# Sheet1.net
KiCad netlist of a schematic drawn in Altium Designer
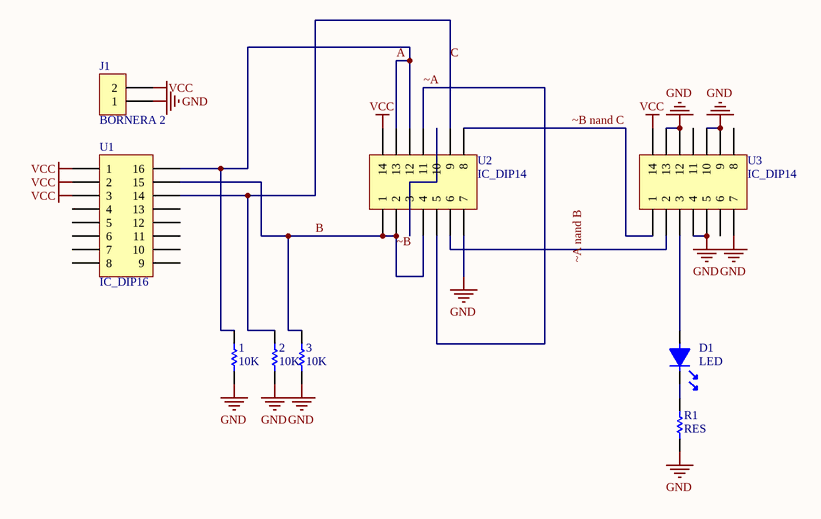
[diagram p0: Sheet1.SchDoc]

(export (version "E")
  (design (tool "Eeschema 10.0.6"))
  (components
    (comp (ref "1") (value "10K") (footprint "RES400") (libsource (lib "LIBEBAL") (part "RES")))
    (comp (ref "2") (value "10K") (footprint "RES400") (libsource (lib "LIBEBAL") (part "RES")))
    (comp (ref "3") (value "10K") (footprint "RES400") (libsource (lib "LIBEBAL") (part "RES")))
    (comp (ref "D1") (value "LED") (footprint "LED3") (libsource (lib "LIBEBAL") (part "LED")))
    (comp (ref "J1")
      (value "BORNERA 2")
      (footprint "BORNERA2")
      (libsource (lib "LIBEBAL") (part "BORNERA 2"))
    )
    (comp (ref "R1") (value "RES") (footprint "RES400") (libsource (lib "LIBEBAL") (part "RES")))
    (comp (ref "U1") (value "IC_DIP16") (footprint "DIP16") (libsource (lib "LIBEBAL") (part "IC_DIP16")))
    (comp (ref "U2") (value "IC_DIP14") (footprint "DIP14") (libsource (lib "LIBEBAL") (part "IC_DIP14")))
    (comp (ref "U3") (value "IC_DIP14") (footprint "DIP14") (libsource (lib "LIBEBAL") (part "IC_DIP14")))
  )
  (nets
    (net (code "1") (name "/A") (class "Default")
      (node (ref "1") (pin "1") (pinfunction "1_1") (pintype "passive"))
      (node (ref "U1") (pin "16") (pinfunction "16_16") (pintype "passive"))
      (node (ref "U2") (pin "12") (pinfunction "12_12") (pintype "passive"))
      (node (ref "U2") (pin "13") (pinfunction "13_13") (pintype "passive"))
    )
    (net (code "2") (name "/B") (class "Default")
      (node (ref "3") (pin "1") (pinfunction "1_1") (pintype "passive"))
      (node (ref "U1") (pin "15") (pinfunction "15_15") (pintype "passive"))
      (node (ref "U2") (pin "1") (pinfunction "1_1") (pintype "passive"))
      (node (ref "U2") (pin "2") (pinfunction "2_2") (pintype "passive"))
      (node (ref "U2") (pin "4") (pinfunction "4_4") (pintype "passive"))
    )
    (net (code "3") (name "/C") (class "Default")
      (node (ref "2") (pin "1") (pinfunction "1_1") (pintype "passive"))
      (node (ref "U1") (pin "14") (pinfunction "14_14") (pintype "passive"))
      (node (ref "U2") (pin "9") (pinfunction "9_9") (pintype "passive"))
    )
    (net (code "4") (name "/~A") (class "Default")
      (node (ref "U2") (pin "11") (pinfunction "11_11") (pintype "passive"))
      (node (ref "U2") (pin "5") (pinfunction "5_5") (pintype "passive"))
    )
    (net (code "6") (name "/~B nand C") (class "Default")
      (node (ref "U2") (pin "8") (pinfunction "8_8") (pintype "passive"))
      (node (ref "U3") (pin "1") (pinfunction "1_1") (pintype "passive"))
    )
    (net (code "7") (name "GND") (class "Default")
      (node (ref "1") (pin "2") (pinfunction "2_2") (pintype "passive"))
      (node (ref "2") (pin "2") (pinfunction "2_2") (pintype "passive"))
      (node (ref "3") (pin "2") (pinfunction "2_2") (pintype "passive"))
      (node (ref "J1") (pin "1") (pinfunction "1_1") (pintype "passive"))
      (node (ref "R1") (pin "1") (pinfunction "1_1") (pintype "passive"))
      (node (ref "U2") (pin "7") (pinfunction "7_7") (pintype "passive"))
      (node (ref "U3") (pin "10") (pinfunction "10_10") (pintype "passive"))
      (node (ref "U3") (pin "12") (pinfunction "12_12") (pintype "passive"))
      (node (ref "U3") (pin "13") (pinfunction "13_13") (pintype "passive"))
      (node (ref "U3") (pin "4") (pinfunction "4_4") (pintype "passive"))
      (node (ref "U3") (pin "5") (pinfunction "5_5") (pintype "passive"))
      (node (ref "U3") (pin "7") (pinfunction "7_7") (pintype "passive"))
      (node (ref "U3") (pin "9") (pinfunction "9_9") (pintype "passive"))
    )
    (net (code "8") (name "Net-(D1-Pad1)") (class "Default")
      (node (ref "D1") (pin "1") (pinfunction "1_1") (pintype "passive"))
      (node (ref "U3") (pin "3") (pinfunction "3_3") (pintype "passive"))
    )
    (net (code "9") (name "Net-(D1-Pad2)") (class "Default")
      (node (ref "D1") (pin "2") (pinfunction "2_2") (pintype "passive"))
      (node (ref "R1") (pin "2") (pinfunction "2_2") (pintype "passive"))
    )
    (net (code "10") (name "Net-(U2-Pad6)") (class "Default")
      (node (ref "U2") (pin "6") (pinfunction "6_6") (pintype "passive"))
      (node (ref "U3") (pin "2") (pinfunction "2_2") (pintype "passive"))
    )
    (net (code "11") (name "Net-(U2-Pad10)") (class "Default")
      (node (ref "U2") (pin "10") (pinfunction "10_10") (pintype "passive"))
      (node (ref "U2") (pin "3") (pinfunction "3_3") (pintype "passive"))
    )
    (net (code "12") (name "VCC") (class "Default")
      (node (ref "J1") (pin "2") (pinfunction "2_2") (pintype "passive"))
      (node (ref "U1") (pin "1") (pinfunction "1_1") (pintype "passive"))
      (node (ref "U1") (pin "2") (pinfunction "2_2") (pintype "passive"))
      (node (ref "U1") (pin "3") (pinfunction "3_3") (pintype "passive"))
      (node (ref "U2") (pin "14") (pinfunction "14_14") (pintype "passive"))
      (node (ref "U3") (pin "14") (pinfunction "14_14") (pintype "passive"))
    )
    (net (code "13") (name "unconnected-(U1-Pad4)") (class "Default")
      (node (ref "U1") (pin "4") (pinfunction "4_4") (pintype "passive"))
    )
    (net (code "14") (name "unconnected-(U1-Pad5)") (class "Default")
      (node (ref "U1") (pin "5") (pinfunction "5_5") (pintype "passive"))
    )
    (net (code "15") (name "unconnected-(U1-Pad6)") (class "Default")
      (node (ref "U1") (pin "6") (pinfunction "6_6") (pintype "passive"))
    )
    (net (code "16") (name "unconnected-(U1-Pad7)") (class "Default")
      (node (ref "U1") (pin "7") (pinfunction "7_7") (pintype "passive"))
    )
    (net (code "17") (name "unconnected-(U1-Pad8)") (class "Default")
      (node (ref "U1") (pin "8") (pinfunction "8_8") (pintype "passive"))
    )
    (net (code "18") (name "unconnected-(U1-Pad9)") (class "Default")
      (node (ref "U1") (pin "9") (pinfunction "9_9") (pintype "passive"))
    )
    (net (code "19") (name "unconnected-(U1-Pad10)") (class "Default")
      (node (ref "U1") (pin "10") (pinfunction "10_10") (pintype "passive"))
    )
    (net (code "20") (name "unconnected-(U1-Pad11)") (class "Default")
      (node (ref "U1") (pin "11") (pinfunction "11_11") (pintype "passive"))
    )
    (net (code "21") (name "unconnected-(U1-Pad12)") (class "Default")
      (node (ref "U1") (pin "12") (pinfunction "12_12") (pintype "passive"))
    )
    (net (code "22") (name "unconnected-(U1-Pad13)") (class "Default")
      (node (ref "U1") (pin "13") (pinfunction "13_13") (pintype "passive"))
    )
    (net (code "23") (name "unconnected-(U3-Pad6)") (class "Default")
      (node (ref "U3") (pin "6") (pinfunction "6_6") (pintype "passive"))
    )
    (net (code "24") (name "unconnected-(U3-Pad8)") (class "Default")
      (node (ref "U3") (pin "8") (pinfunction "8_8") (pintype "passive"))
    )
    (net (code "25") (name "unconnected-(U3-Pad11)") (class "Default")
      (node (ref "U3") (pin "11") (pinfunction "11_11") (pintype "passive"))
    )
  )
)
